# 12V_Input_Circuitry.net
KiCad netlist of a schematic drawn in Altium Designer
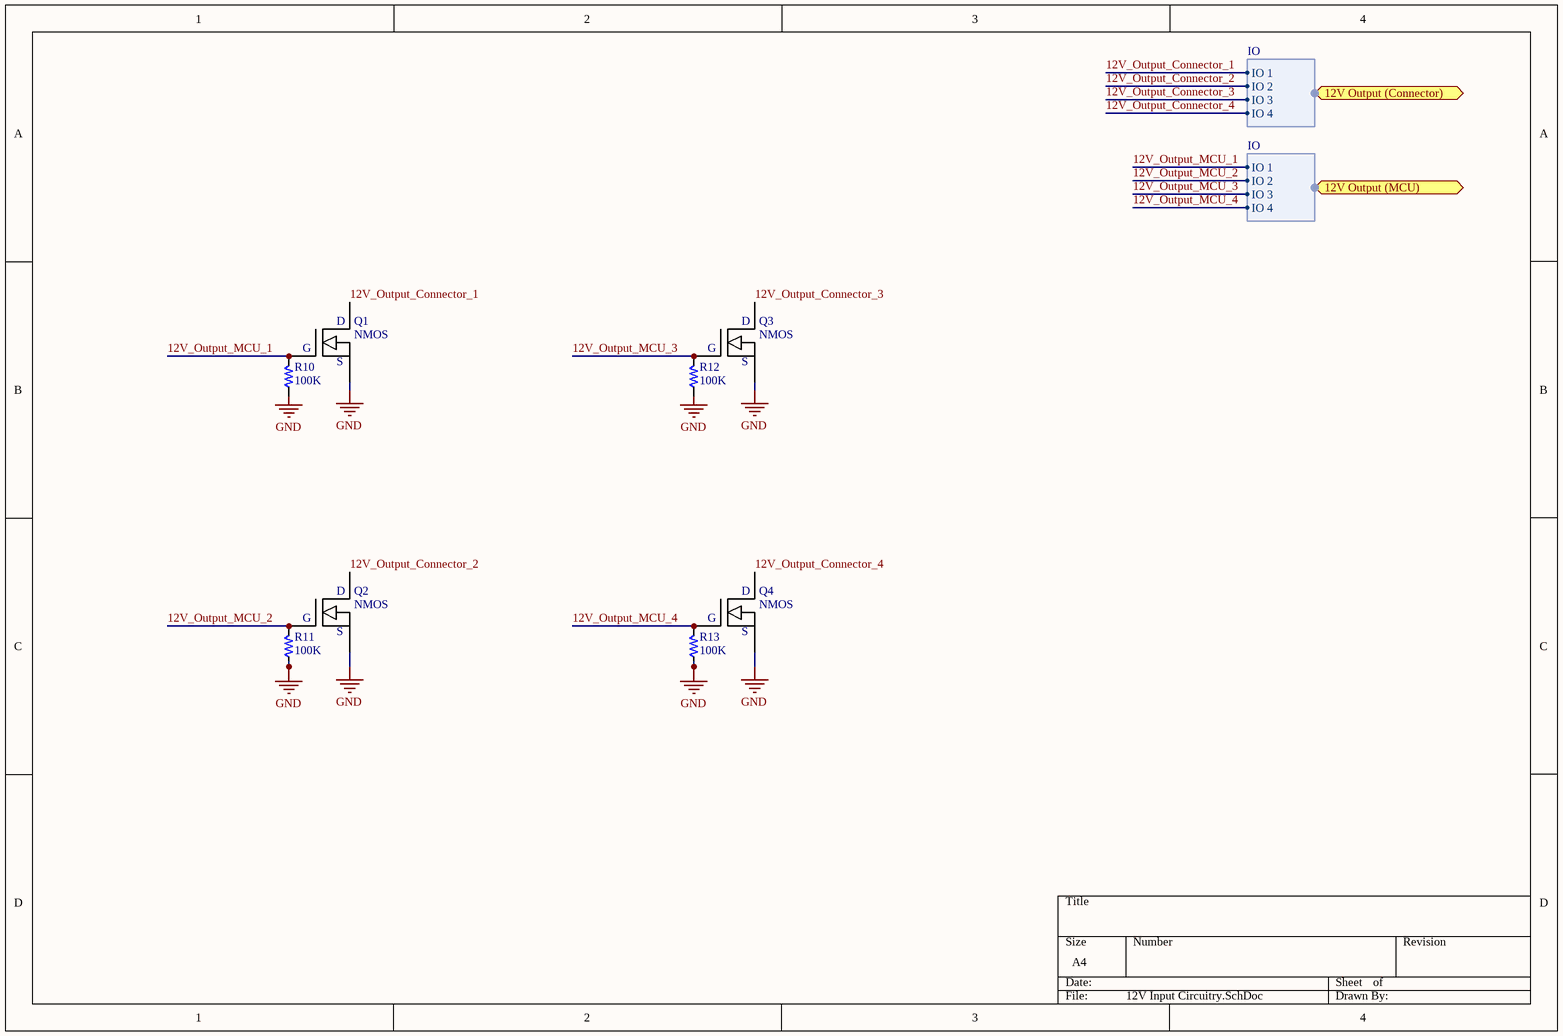
[diagram p0: 12V Input Circuitry.SchDoc]

(export (version "E")
  (design (tool "Eeschema 10.0.6"))
  (components
    (comp (ref "Q1")
      (value "NMOS")
      (footprint "NMOS - SSM3K333R - SOTFL95P180X88-3M")
      (libsource (lib "NMOS - SSM3K333R - SOTFL95P180X88-3M") (part "NMOS - SSM3K333R"))
    )
    (comp (ref "Q2")
      (value "NMOS")
      (footprint "NMOS - SSM3K333R - SOTFL95P180X88-3M")
      (libsource (lib "NMOS - SSM3K333R - SOTFL95P180X88-3M") (part "NMOS - SSM3K333R"))
    )
    (comp (ref "Q3")
      (value "NMOS")
      (footprint "NMOS - SSM3K333R - SOTFL95P180X88-3M")
      (libsource (lib "NMOS - SSM3K333R - SOTFL95P180X88-3M") (part "NMOS - SSM3K333R"))
    )
    (comp (ref "Q4")
      (value "NMOS")
      (footprint "NMOS - SSM3K333R - SOTFL95P180X88-3M")
      (libsource (lib "NMOS - SSM3K333R - SOTFL95P180X88-3M") (part "NMOS - SSM3K333R"))
    )
    (comp (ref "R10")
      (value "100K")
      (footprint "PCB_GENERIC_SMD_0603")
      (description "RES 0603 100K 5% 63mW")
      (fields (field (name "TOLERANCE") "5%") (field (name "POWER") "63mW"))
      (libsource (lib "RES-0603") (part "R060-00104-05"))
    )
    (comp (ref "R11")
      (value "100K")
      (footprint "PCB_GENERIC_SMD_0603")
      (description "RES 0603 100K 5% 63mW")
      (fields (field (name "TOLERANCE") "5%") (field (name "POWER") "63mW"))
      (libsource (lib "RES-0603") (part "R060-00104-05"))
    )
    (comp (ref "R12")
      (value "100K")
      (footprint "PCB_GENERIC_SMD_0603")
      (description "RES 0603 100K 5% 63mW")
      (fields (field (name "TOLERANCE") "5%") (field (name "POWER") "63mW"))
      (libsource (lib "RES-0603") (part "R060-00104-05"))
    )
    (comp (ref "R13")
      (value "100K")
      (footprint "PCB_GENERIC_SMD_0603")
      (description "RES 0603 100K 5% 63mW")
      (fields (field (name "TOLERANCE") "5%") (field (name "POWER") "63mW"))
      (libsource (lib "RES-0603") (part "R060-00104-05"))
    )
  )
  (nets
    (net (code "2") (name "/12V_Output_Connector_1") (class "Default")
      (node (ref "Q1") (pin "3") (pinfunction "D_3") (pintype "passive"))
    )
    (net (code "3") (name "/12V_Output_Connector_2") (class "Default")
      (node (ref "Q2") (pin "3") (pinfunction "D_3") (pintype "passive"))
    )
    (net (code "4") (name "/12V_Output_Connector_3") (class "Default")
      (node (ref "Q3") (pin "3") (pinfunction "D_3") (pintype "passive"))
    )
    (net (code "5") (name "/12V_Output_Connector_4") (class "Default")
      (node (ref "Q4") (pin "3") (pinfunction "D_3") (pintype "passive"))
    )
    (net (code "6") (name "/12V_Output_MCU_1") (class "Default")
      (node (ref "Q1") (pin "1") (pinfunction "G_1") (pintype "passive"))
      (node (ref "R10") (pin "2") (pinfunction "2_2") (pintype "passive"))
    )
    (net (code "7") (name "/12V_Output_MCU_2") (class "Default")
      (node (ref "Q2") (pin "1") (pinfunction "G_1") (pintype "passive"))
      (node (ref "R11") (pin "2") (pinfunction "2_2") (pintype "passive"))
    )
    (net (code "8") (name "/12V_Output_MCU_3") (class "Default")
      (node (ref "Q3") (pin "1") (pinfunction "G_1") (pintype "passive"))
      (node (ref "R12") (pin "2") (pinfunction "2_2") (pintype "passive"))
    )
    (net (code "9") (name "/12V_Output_MCU_4") (class "Default")
      (node (ref "Q4") (pin "1") (pinfunction "G_1") (pintype "passive"))
      (node (ref "R13") (pin "2") (pinfunction "2_2") (pintype "passive"))
    )
    (net (code "11") (name "GND") (class "Default")
      (node (ref "Q1") (pin "2") (pinfunction "S_2") (pintype "passive"))
      (node (ref "Q2") (pin "2") (pinfunction "S_2") (pintype "passive"))
      (node (ref "Q3") (pin "2") (pinfunction "S_2") (pintype "passive"))
      (node (ref "Q4") (pin "2") (pinfunction "S_2") (pintype "passive"))
      (node (ref "R11") (pin "1") (pinfunction "1_1") (pintype "passive"))
      (node (ref "R13") (pin "1") (pinfunction "1_1") (pintype "passive"))
    )
    (net (code "12") (name "unconnected-(R10-Pad1)") (class "Default")
      (node (ref "R10") (pin "1") (pinfunction "1_1") (pintype "passive"))
    )
    (net (code "13") (name "unconnected-(R12-Pad1)") (class "Default")
      (node (ref "R12") (pin "1") (pinfunction "1_1") (pintype "passive"))
    )
  )
)
